# RGMII_PHY.net
KiCad netlist of a schematic drawn in Altium Designer
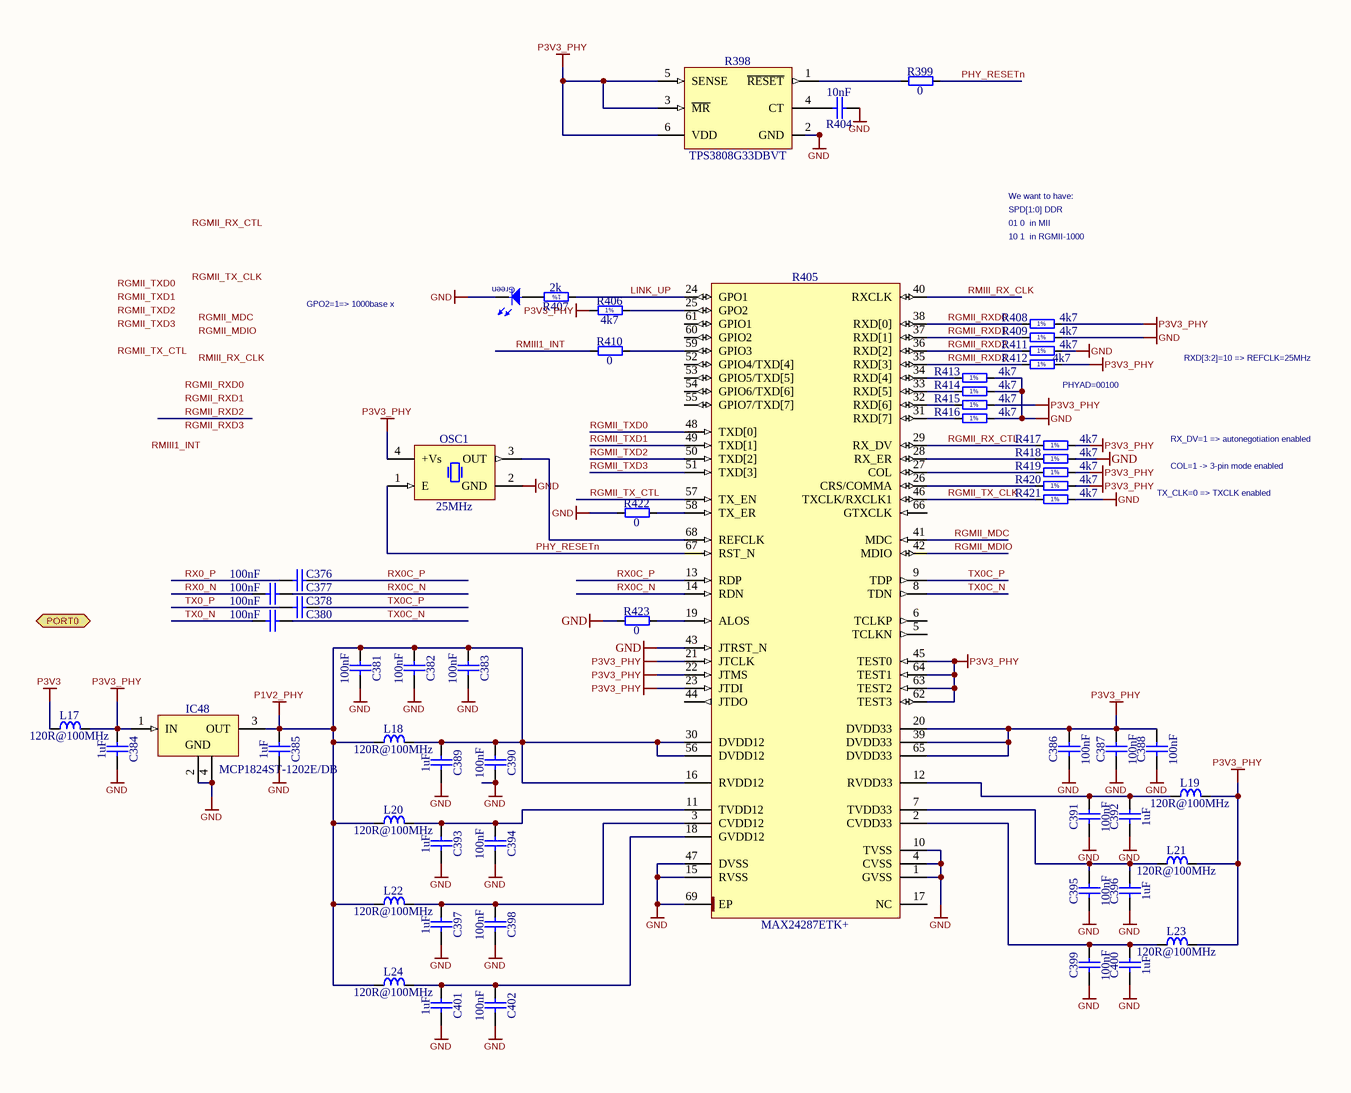
[diagram p0: RGMII_PHY.SchDoc]

(export (version "E")
  (design (tool "Eeschema 10.0.6"))
  (components
    (comp (ref "C376")
      (value "100nF")
      (footprint "CAPC0603X33N")
      (description "Non-polarised capacitor")
      (fields
        (field (name "MANUFACTURER PART NUMBER") "CC0201_100NF_6.3V_10%_X5R")
        (field (name "MANUFACTURER") "GENERIC")
        (field (name "AUTHOR") "CERN DEM JLC")
      )
      (libsource (lib "Capacitors") (part "Capacitor - non polarized"))
    )
    (comp (ref "C377")
      (value "100nF")
      (footprint "CAPC0603X33N")
      (description "Non-polarised capacitor")
      (fields
        (field (name "MANUFACTURER PART NUMBER") "CC0201_100NF_6.3V_10%_X5R")
        (field (name "MANUFACTURER") "GENERIC")
        (field (name "AUTHOR") "CERN DEM JLC")
      )
      (libsource (lib "Capacitors") (part "Capacitor - non polarized"))
    )
    (comp (ref "C378")
      (value "100nF")
      (footprint "CAPC0603X33N")
      (description "Non-polarised capacitor")
      (fields
        (field (name "MANUFACTURER PART NUMBER") "CC0201_100NF_6.3V_10%_X5R")
        (field (name "MANUFACTURER") "GENERIC")
        (field (name "AUTHOR") "CERN DEM JLC")
      )
      (libsource (lib "Capacitors") (part "Capacitor - non polarized"))
    )
    (comp (ref "C380")
      (value "100nF")
      (footprint "CAPC0603X33N")
      (description "Non-polarised capacitor")
      (fields
        (field (name "MANUFACTURER PART NUMBER") "CC0201_100NF_6.3V_10%_X5R")
        (field (name "MANUFACTURER") "GENERIC")
        (field (name "AUTHOR") "CERN DEM JLC")
      )
      (libsource (lib "Capacitors") (part "Capacitor - non polarized"))
    )
    (comp (ref "C381")
      (value "100nF")
      (footprint "CAPC0603X33N")
      (description "Non-polarised capacitor")
      (fields
        (field (name "MANUFACTURER PART NUMBER") "CC0201_100NF_6.3V_10%_X5R")
        (field (name "MANUFACTURER") "GENERIC")
        (field (name "AUTHOR") "CERN DEM JLC")
      )
      (libsource (lib "Capacitors") (part "Capacitor - non polarized"))
    )
    (comp (ref "C382")
      (value "100nF")
      (footprint "CAPC0603X33N")
      (description "Non-polarised capacitor")
      (fields
        (field (name "MANUFACTURER PART NUMBER") "CC0201_100NF_6.3V_10%_X5R")
        (field (name "MANUFACTURER") "GENERIC")
        (field (name "AUTHOR") "CERN DEM JLC")
      )
      (libsource (lib "Capacitors") (part "Capacitor - non polarized"))
    )
    (comp (ref "C383")
      (value "100nF")
      (footprint "CAPC0603X33N")
      (description "Non-polarised capacitor")
      (fields
        (field (name "MANUFACTURER PART NUMBER") "CC0201_100NF_6.3V_10%_X5R")
        (field (name "MANUFACTURER") "GENERIC")
        (field (name "AUTHOR") "CERN DEM JLC")
      )
      (libsource (lib "Capacitors") (part "Capacitor - non polarized"))
    )
    (comp (ref "C384")
      (value "1uF")
      (footprint "CAPC1005X55N")
      (description "Non-polarised capacitor")
      (fields
        (field (name "MANUFACTURER PART NUMBER") "CC0402_1UF_16V_10%_X5R")
        (field (name "MANUFACTURER") "GENERIC")
        (field (name "AUTHOR") "CERN DEM JLC")
      )
      (libsource (lib "Capacitors") (part "Capacitor - non polarized"))
    )
    (comp (ref "C385")
      (value "1uF")
      (footprint "CAPC1005X55N")
      (description "Non-polarised capacitor")
      (fields
        (field (name "MANUFACTURER PART NUMBER") "CC0402_1UF_16V_10%_X5R")
        (field (name "MANUFACTURER") "GENERIC")
        (field (name "AUTHOR") "CERN DEM JLC")
      )
      (libsource (lib "Capacitors") (part "Capacitor - non polarized"))
    )
    (comp (ref "C386")
      (value "100nF")
      (footprint "CAPC0603X33N")
      (description "Non-polarised capacitor")
      (fields
        (field (name "MANUFACTURER PART NUMBER") "CC0201_100NF_6.3V_10%_X5R")
        (field (name "MANUFACTURER") "GENERIC")
        (field (name "AUTHOR") "CERN DEM JLC")
      )
      (libsource (lib "Capacitors") (part "Capacitor - non polarized"))
    )
    (comp (ref "C387")
      (value "100nF")
      (footprint "CAPC0603X33N")
      (description "Non-polarised capacitor")
      (fields
        (field (name "MANUFACTURER PART NUMBER") "CC0201_100NF_6.3V_10%_X5R")
        (field (name "MANUFACTURER") "GENERIC")
        (field (name "AUTHOR") "CERN DEM JLC")
      )
      (libsource (lib "Capacitors") (part "Capacitor - non polarized"))
    )
    (comp (ref "C388")
      (value "100nF")
      (footprint "CAPC0603X33N")
      (description "Non-polarised capacitor")
      (fields
        (field (name "MANUFACTURER PART NUMBER") "CC0201_100NF_6.3V_10%_X5R")
        (field (name "MANUFACTURER") "GENERIC")
        (field (name "AUTHOR") "CERN DEM JLC")
      )
      (libsource (lib "Capacitors") (part "Capacitor - non polarized"))
    )
    (comp (ref "C389")
      (value "1uF")
      (footprint "CAPC1005X55N")
      (description "Non-polarised capacitor")
      (fields
        (field (name "MANUFACTURER PART NUMBER") "CC0402_1UF_16V_10%_X5R")
        (field (name "MANUFACTURER") "GENERIC")
        (field (name "AUTHOR") "CERN DEM JLC")
      )
      (libsource (lib "Capacitors") (part "Capacitor - non polarized"))
    )
    (comp (ref "C390")
      (value "100nF")
      (footprint "CAPC0603X33N")
      (description "Non-polarised capacitor")
      (fields
        (field (name "MANUFACTURER PART NUMBER") "CC0201_100NF_6.3V_10%_X5R")
        (field (name "MANUFACTURER") "GENERIC")
        (field (name "AUTHOR") "CERN DEM JLC")
      )
      (libsource (lib "Capacitors") (part "Capacitor - non polarized"))
    )
    (comp (ref "C391")
      (value "100nF")
      (footprint "CAPC0603X33N")
      (description "Non-polarised capacitor")
      (fields
        (field (name "MANUFACTURER PART NUMBER") "CC0201_100NF_6.3V_10%_X5R")
        (field (name "MANUFACTURER") "GENERIC")
        (field (name "AUTHOR") "CERN DEM JLC")
      )
      (libsource (lib "Capacitors") (part "Capacitor - non polarized"))
    )
    (comp (ref "C392")
      (value "1uF")
      (footprint "CAPC1005X55N")
      (description "Non-polarised capacitor")
      (fields
        (field (name "MANUFACTURER PART NUMBER") "CC0402_1UF_16V_10%_X5R")
        (field (name "MANUFACTURER") "GENERIC")
        (field (name "AUTHOR") "CERN DEM JLC")
      )
      (libsource (lib "Capacitors") (part "Capacitor - non polarized"))
    )
    (comp (ref "C393")
      (value "1uF")
      (footprint "CAPC1005X55N")
      (description "Non-polarised capacitor")
      (fields
        (field (name "MANUFACTURER PART NUMBER") "CC0402_1UF_16V_10%_X5R")
        (field (name "MANUFACTURER") "GENERIC")
        (field (name "AUTHOR") "CERN DEM JLC")
      )
      (libsource (lib "Capacitors") (part "Capacitor - non polarized"))
    )
    (comp (ref "C394")
      (value "100nF")
      (footprint "CAPC0603X33N")
      (description "Non-polarised capacitor")
      (fields
        (field (name "MANUFACTURER PART NUMBER") "CC0201_100NF_6.3V_10%_X5R")
        (field (name "MANUFACTURER") "GENERIC")
        (field (name "AUTHOR") "CERN DEM JLC")
      )
      (libsource (lib "Capacitors") (part "Capacitor - non polarized"))
    )
    (comp (ref "C395")
      (value "100nF")
      (footprint "CAPC0603X33N")
      (description "Non-polarised capacitor")
      (fields
        (field (name "MANUFACTURER PART NUMBER") "CC0201_100NF_6.3V_10%_X5R")
        (field (name "MANUFACTURER") "GENERIC")
        (field (name "AUTHOR") "CERN DEM JLC")
      )
      (libsource (lib "Capacitors") (part "Capacitor - non polarized"))
    )
    (comp (ref "C396")
      (value "1uF")
      (footprint "CAPC1005X55N")
      (description "Non-polarised capacitor")
      (fields
        (field (name "MANUFACTURER PART NUMBER") "CC0402_1UF_16V_10%_X5R")
        (field (name "MANUFACTURER") "GENERIC")
        (field (name "AUTHOR") "CERN DEM JLC")
      )
      (libsource (lib "Capacitors") (part "Capacitor - non polarized"))
    )
    (comp (ref "C397")
      (value "1uF")
      (footprint "CAPC1005X55N")
      (description "Non-polarised capacitor")
      (fields
        (field (name "MANUFACTURER PART NUMBER") "CC0402_1UF_16V_10%_X5R")
        (field (name "MANUFACTURER") "GENERIC")
        (field (name "AUTHOR") "CERN DEM JLC")
      )
      (libsource (lib "Capacitors") (part "Capacitor - non polarized"))
    )
    (comp (ref "C398")
      (value "100nF")
      (footprint "CAPC0603X33N")
      (description "Non-polarised capacitor")
      (fields
        (field (name "MANUFACTURER PART NUMBER") "CC0201_100NF_6.3V_10%_X5R")
        (field (name "MANUFACTURER") "GENERIC")
        (field (name "AUTHOR") "CERN DEM JLC")
      )
      (libsource (lib "Capacitors") (part "Capacitor - non polarized"))
    )
    (comp (ref "C399")
      (value "100nF")
      (footprint "CAPC0603X33N")
      (description "Non-polarised capacitor")
      (fields
        (field (name "MANUFACTURER PART NUMBER") "CC0201_100NF_6.3V_10%_X5R")
        (field (name "MANUFACTURER") "GENERIC")
        (field (name "AUTHOR") "CERN DEM JLC")
      )
      (libsource (lib "Capacitors") (part "Capacitor - non polarized"))
    )
    (comp (ref "C400")
      (value "1uF")
      (footprint "CAPC1005X55N")
      (description "Non-polarised capacitor")
      (fields
        (field (name "MANUFACTURER PART NUMBER") "CC0402_1UF_16V_10%_X5R")
        (field (name "MANUFACTURER") "GENERIC")
        (field (name "AUTHOR") "CERN DEM JLC")
      )
      (libsource (lib "Capacitors") (part "Capacitor - non polarized"))
    )
    (comp (ref "C401")
      (value "1uF")
      (footprint "CAPC1005X55N")
      (description "Non-polarised capacitor")
      (fields
        (field (name "MANUFACTURER PART NUMBER") "CC0402_1UF_16V_10%_X5R")
        (field (name "MANUFACTURER") "GENERIC")
        (field (name "AUTHOR") "CERN DEM JLC")
      )
      (libsource (lib "Capacitors") (part "Capacitor - non polarized"))
    )
    (comp (ref "C402")
      (value "100nF")
      (footprint "CAPC0603X33N")
      (description "Non-polarised capacitor")
      (fields
        (field (name "MANUFACTURER PART NUMBER") "CC0201_100NF_6.3V_10%_X5R")
        (field (name "MANUFACTURER") "GENERIC")
        (field (name "AUTHOR") "CERN DEM JLC")
      )
      (libsource (lib "Capacitors") (part "Capacitor - non polarized"))
    )
    (comp (ref "IC48")
      (value "MCP1824ST-1202E/DB")
      (footprint "SOT230P700X180-4N")
      (description "3-Terminal Regulator 1=IN 2=GND 3=OUT 4=GND")
      (fields (field (name "MANUFACTURER") "MICROCHIP TECHNOLOGY") (field (name "AUTHOR") "CERN DEM JLC"))
      (libsource (lib "ICs And Semiconductors") (part "REG3+1 1IN-2GND-3OUT+4GND"))
    )
    (comp (ref "L17")
      (value "120R@100MHz")
      (footprint "INDC1005X55N")
      (description "Inductor")
      (fields
        (field (name "MANUFACTURER PART NUMBER") "BLM15PX121SN1D")
        (field (name "MANUFACTURER") "MURATA")
        (field (name "AUTHOR") "CERN DEM JMW")
      )
      (libsource (lib "") (part "Inductor_1"))
    )
    (comp (ref "L18")
      (value "120R@100MHz")
      (footprint "INDC1005X55N")
      (description "Inductor")
      (fields
        (field (name "MANUFACTURER PART NUMBER") "BLM15PX121SN1D")
        (field (name "MANUFACTURER") "MURATA")
        (field (name "AUTHOR") "CERN DEM JMW")
      )
      (libsource (lib "Inductors & Transformers") (part "Inductor"))
    )
    (comp (ref "L19")
      (value "120R@100MHz")
      (footprint "INDC1005X55N")
      (description "Inductor")
      (fields
        (field (name "MANUFACTURER PART NUMBER") "BLM15PX121SN1D")
        (field (name "MANUFACTURER") "MURATA")
        (field (name "AUTHOR") "CERN DEM JMW")
      )
      (libsource (lib "") (part "Inductor_1"))
    )
    (comp (ref "L20")
      (value "120R@100MHz")
      (footprint "INDC1005X55N")
      (description "Inductor")
      (fields
        (field (name "MANUFACTURER PART NUMBER") "BLM15PX121SN1D")
        (field (name "MANUFACTURER") "MURATA")
        (field (name "AUTHOR") "CERN DEM JMW")
      )
      (libsource (lib "Inductors & Transformers") (part "Inductor"))
    )
    (comp (ref "L21")
      (value "120R@100MHz")
      (footprint "INDC1005X55N")
      (description "Inductor")
      (fields
        (field (name "MANUFACTURER PART NUMBER") "BLM15PX121SN1D")
        (field (name "MANUFACTURER") "MURATA")
        (field (name "AUTHOR") "CERN DEM JMW")
      )
      (libsource (lib "") (part "Inductor_1"))
    )
    (comp (ref "L22")
      (value "120R@100MHz")
      (footprint "INDC1005X55N")
      (description "Inductor")
      (fields
        (field (name "MANUFACTURER PART NUMBER") "BLM15PX121SN1D")
        (field (name "MANUFACTURER") "MURATA")
        (field (name "AUTHOR") "CERN DEM JMW")
      )
      (libsource (lib "Inductors & Transformers") (part "Inductor"))
    )
    (comp (ref "L23")
      (value "120R@100MHz")
      (footprint "INDC1005X55N")
      (description "Inductor")
      (fields
        (field (name "MANUFACTURER PART NUMBER") "BLM15PX121SN1D")
        (field (name "MANUFACTURER") "MURATA")
        (field (name "AUTHOR") "CERN DEM JMW")
      )
      (libsource (lib "") (part "Inductor_1"))
    )
    (comp (ref "L24")
      (value "120R@100MHz")
      (footprint "INDC1005X55N")
      (description "Inductor")
      (fields
        (field (name "MANUFACTURER PART NUMBER") "BLM15PX121SN1D")
        (field (name "MANUFACTURER") "MURATA")
        (field (name "AUTHOR") "CERN DEM JMW")
      )
      (libsource (lib "Inductors & Transformers") (part "Inductor"))
    )
    (comp (ref "LED1")
      (value "Green")
      (fields
        (field (name "MANUFACTURER PART NUMBER") "LG L29K-G2J1-24-Z")
        (field (name "MANUFACTURER") "OSRAM")
        (field (name "PART NUMBER") "LED_OSRAM_LG L29K-G2J1-24-Z")
        (field (name "AUTHOR") "CERN DEM JLC")
      )
      (libsource (lib "altium-import") (part "root_2__*"))
    )
    (comp (ref "OSC1")
      (value "25MHz")
      (footprint "OSC_IQD_CFPS-73")
      (description "Oscillator 4 pins 1=E 2=GND 3=OUT 4=+Vs")
      (fields
        (field (name "PART NUMBER") "OSC_25MHZ_IQD_LFSPXO018077")
        (field (name "MANUFACTURER") "IQD FREQUENCY PRODUCTS")
        (field (name "AUTHOR") "CERN DEM JLC")
      )
      (libsource (lib "ICs And Semiconductors") (part "Oscillator 1E 2GND 3OUT 4Vs"))
    )
    (comp (ref "R398")
      (value "TPS3808G33DBVT")
      (footprint "SOT95P280X145-6N")
      (description "Low Quiescent Current, Programmable-Delay Supervisory Circuit")
      (fields (field (name "MANUFACTURER") "TEXAS INSTRUMENTS") (field (name "AUTHOR") "CERN DEM JLC"))
      (libsource (lib "ICs And Semiconductors") (part "TPS3808xxxDBV"))
    )
    (comp (ref "R399")
      (value "0")
      (footprint "RESC1005X40N")
      (description "Resistor")
      (fields
        (field (name "MANUFACTURER PART NUMBER") "R0402_0R_JUMPER")
        (field (name "MANUFACTURER") "GENERIC")
        (field (name "AUTHOR") "CERN DEM JLC")
      )
      (libsource (lib "Resistors") (part "Resistor"))
    )
    (comp (ref "R404")
      (value "10nF")
      (footprint "CAPC1005X55N")
      (description "Non-polarised capacitor")
      (fields
        (field (name "MANUFACTURER PART NUMBER") "CC0402_10NF_16V_10%_X7R")
        (field (name "MANUFACTURER") "GENERIC")
        (field (name "AUTHOR") "CERN DEM JLC")
      )
      (libsource (lib "Capacitors") (part "Capacitor - non polarized"))
    )
    (comp (ref "R405")
      (value "MAX24287ETK+")
      (footprint "QFN40P800X800X80-69N-S635")
      (description "1Gbps Parallel-to-Serial MII Converter")
      (fields (field (name "MANUFACTURER") "MAXIM") (field (name "AUTHOR") "CERN DEM BC"))
      (libsource (lib "ICs And Semiconductors") (part "MAX24287"))
    )
    (comp (ref "R406")
      (value "4k7")
      (footprint "RESC1005X40N")
      (description "Resistor - 1%")
      (fields
        (field (name "MANUFACTURER PART NUMBER") "R0402_4K7_1%_0.0625W_100PPM")
        (field (name "MANUFACTURER") "GENERIC")
        (field (name "AUTHOR") "CERN DEM JLC")
      )
      (libsource (lib "Resistors") (part "Resistor - 1%"))
    )
    (comp (ref "R407")
      (value "2k")
      (footprint "RESC1005X40N")
      (description "Resistor - 1%")
      (fields
        (field (name "MANUFACTURER PART NUMBER") "R0402_2K_1%_0.0625W_100PPM")
        (field (name "MANUFACTURER") "GENERIC")
        (field (name "AUTHOR") "CERN DEM JLC")
      )
      (libsource (lib "Resistors") (part "Resistor - 1%"))
    )
    (comp (ref "R408")
      (value "4k7")
      (footprint "RESC1005X40N")
      (description "Resistor - 1%")
      (fields
        (field (name "MANUFACTURER PART NUMBER") "R0402_4K7_1%_0.0625W_100PPM")
        (field (name "MANUFACTURER") "GENERIC")
        (field (name "AUTHOR") "CERN DEM JLC")
      )
      (libsource (lib "Resistors") (part "Resistor - 1%"))
    )
    (comp (ref "R409")
      (value "4k7")
      (footprint "RESC1005X40N")
      (description "Resistor - 1%")
      (fields
        (field (name "MANUFACTURER PART NUMBER") "R0402_4K7_1%_0.0625W_100PPM")
        (field (name "MANUFACTURER") "GENERIC")
        (field (name "AUTHOR") "CERN DEM JLC")
      )
      (libsource (lib "Resistors") (part "Resistor - 1%"))
    )
    (comp (ref "R410")
      (value "0")
      (footprint "RESC1005X40N")
      (description "Resistor")
      (fields
        (field (name "MANUFACTURER PART NUMBER") "R0402_0R_JUMPER")
        (field (name "MANUFACTURER") "GENERIC")
        (field (name "AUTHOR") "CERN DEM JLC")
      )
      (libsource (lib "Resistors") (part "Resistor"))
    )
    (comp (ref "R411")
      (value "4k7")
      (footprint "RESC1005X40N")
      (description "Resistor - 1%")
      (fields
        (field (name "MANUFACTURER PART NUMBER") "R0402_4K7_1%_0.0625W_100PPM")
        (field (name "MANUFACTURER") "GENERIC")
        (field (name "AUTHOR") "CERN DEM JLC")
      )
      (libsource (lib "Resistors") (part "Resistor - 1%"))
    )
    (comp (ref "R412")
      (value "4k7")
      (footprint "RESC1005X40N")
      (description "Resistor - 1%")
      (fields
        (field (name "MANUFACTURER PART NUMBER") "R0402_4K7_1%_0.0625W_100PPM")
        (field (name "MANUFACTURER") "GENERIC")
        (field (name "AUTHOR") "CERN DEM JLC")
      )
      (libsource (lib "Resistors") (part "Resistor - 1%"))
    )
    (comp (ref "R413")
      (value "4k7")
      (footprint "RESC1005X40N")
      (description "Resistor - 1%")
      (fields
        (field (name "MANUFACTURER PART NUMBER") "R0402_4K7_1%_0.0625W_100PPM")
        (field (name "MANUFACTURER") "GENERIC")
        (field (name "AUTHOR") "CERN DEM JLC")
      )
      (libsource (lib "Resistors") (part "Resistor - 1%"))
    )
    (comp (ref "R414")
      (value "4k7")
      (footprint "RESC1005X40N")
      (description "Resistor - 1%")
      (fields
        (field (name "MANUFACTURER PART NUMBER") "R0402_4K7_1%_0.0625W_100PPM")
        (field (name "MANUFACTURER") "GENERIC")
        (field (name "AUTHOR") "CERN DEM JLC")
      )
      (libsource (lib "Resistors") (part "Resistor - 1%"))
    )
    (comp (ref "R415")
      (value "4k7")
      (footprint "RESC1005X40N")
      (description "Resistor - 1%")
      (fields
        (field (name "MANUFACTURER PART NUMBER") "R0402_4K7_1%_0.0625W_100PPM")
        (field (name "MANUFACTURER") "GENERIC")
        (field (name "AUTHOR") "CERN DEM JLC")
      )
      (libsource (lib "Resistors") (part "Resistor - 1%"))
    )
    (comp (ref "R416")
      (value "4k7")
      (footprint "RESC1005X40N")
      (description "Resistor - 1%")
      (fields
        (field (name "MANUFACTURER PART NUMBER") "R0402_4K7_1%_0.0625W_100PPM")
        (field (name "MANUFACTURER") "GENERIC")
        (field (name "AUTHOR") "CERN DEM JLC")
      )
      (libsource (lib "Resistors") (part "Resistor - 1%"))
    )
    (comp (ref "R417")
      (value "4k7")
      (footprint "RESC1005X40N")
      (description "Resistor - 1%")
      (fields
        (field (name "MANUFACTURER PART NUMBER") "R0402_4K7_1%_0.0625W_100PPM")
        (field (name "MANUFACTURER") "GENERIC")
        (field (name "AUTHOR") "CERN DEM JLC")
      )
      (libsource (lib "Resistors") (part "Resistor - 1%"))
    )
    (comp (ref "R418")
      (value "4k7")
      (footprint "RESC1005X40N")
      (description "Resistor - 1%")
      (fields
        (field (name "MANUFACTURER PART NUMBER") "R0402_4K7_1%_0.0625W_100PPM")
        (field (name "MANUFACTURER") "GENERIC")
        (field (name "AUTHOR") "CERN DEM JLC")
      )
      (libsource (lib "Resistors") (part "Resistor - 1%"))
    )
    (comp (ref "R419")
      (value "4k7")
      (footprint "RESC1005X40N")
      (description "Resistor - 1%")
      (fields
        (field (name "MANUFACTURER PART NUMBER") "R0402_4K7_1%_0.0625W_100PPM")
        (field (name "MANUFACTURER") "GENERIC")
        (field (name "AUTHOR") "CERN DEM JLC")
      )
      (libsource (lib "Resistors") (part "Resistor - 1%"))
    )
    (comp (ref "R420")
      (value "4k7")
      (footprint "RESC1005X40N")
      (description "Resistor - 1%")
      (fields
        (field (name "MANUFACTURER PART NUMBER") "R0402_4K7_1%_0.0625W_100PPM")
        (field (name "MANUFACTURER") "GENERIC")
        (field (name "AUTHOR") "CERN DEM JLC")
      )
      (libsource (lib "Resistors") (part "Resistor - 1%"))
    )
    (comp (ref "R421")
      (value "4k7")
      (footprint "RESC1005X40N")
      (description "Resistor - 1%")
      (fields
        (field (name "MANUFACTURER PART NUMBER") "R0402_4K7_1%_0.0625W_100PPM")
        (field (name "MANUFACTURER") "GENERIC")
        (field (name "AUTHOR") "CERN DEM JLC")
      )
      (libsource (lib "Resistors") (part "Resistor - 1%"))
    )
    (comp (ref "R422")
      (value "0")
      (footprint "RESC1005X40N")
      (description "Resistor")
      (fields
        (field (name "MANUFACTURER PART NUMBER") "R0402_0R_JUMPER")
        (field (name "MANUFACTURER") "GENERIC")
        (field (name "AUTHOR") "CERN DEM JLC")
      )
      (libsource (lib "Resistors") (part "Resistor"))
    )
    (comp (ref "R423")
      (value "0")
      (footprint "RESC1005X40N")
      (description "Resistor")
      (fields
        (field (name "MANUFACTURER PART NUMBER") "R0402_0R_JUMPER")
        (field (name "MANUFACTURER") "GENERIC")
        (field (name "AUTHOR") "CERN DEM JLC")
      )
      (libsource (lib "Resistors") (part "Resistor"))
    )
  )
  (nets
    (net (code "1") (name "/LINK_UP") (class "Default")
      (node (ref "R405") (pin "24") (pinfunction "GPO1_24") (pintype "bidirectional"))
      (node (ref "R407") (pin "1") (pinfunction "1_1") (pintype "passive"))
    )
    (net (code "2") (name "/PHY_RESETn") (class "Default")
      (node (ref "OSC1") (pin "1") (pinfunction "E_1") (pintype "input"))
      (node (ref "R399") (pin "2") (pinfunction "2_2") (pintype "passive"))
      (node (ref "R405") (pin "67") (pinfunction "RST_N_67") (pintype "input"))
    )
    (net (code "4") (name "/RGMII_MDC") (class "Default")
      (node (ref "R405") (pin "41") (pinfunction "MDC_41") (pintype "input"))
    )
    (net (code "5") (name "/RGMII_MDIO") (class "Default")
      (node (ref "R405") (pin "42") (pinfunction "MDIO_42") (pintype "bidirectional"))
    )
    (net (code "6") (name "/RGMII_RXD0") (class "Default")
      (node (ref "R405") (pin "38") (pinfunction "RXD[0]_38") (pintype "bidirectional"))
      (node (ref "R408") (pin "1") (pinfunction "1_1") (pintype "passive"))
    )
    (net (code "7") (name "/RGMII_RXD1") (class "Default")
      (node (ref "R405") (pin "37") (pinfunction "RXD[1]_37") (pintype "bidirectional"))
      (node (ref "R409") (pin "1") (pinfunction "1_1") (pintype "passive"))
    )
    (net (code "8") (name "/RGMII_RXD2") (class "Default")
      (node (ref "R405") (pin "36") (pinfunction "RXD[2]_36") (pintype "bidirectional"))
      (node (ref "R411") (pin "1") (pinfunction "1_1") (pintype "passive"))
    )
    (net (code "9") (name "/RGMII_RXD3") (class "Default")
      (node (ref "R405") (pin "35") (pinfunction "RXD[3]_35") (pintype "bidirectional"))
      (node (ref "R412") (pin "1") (pinfunction "1_1") (pintype "passive"))
    )
    (net (code "10") (name "/RGMII_RX_CTL") (class "Default")
      (node (ref "R405") (pin "29") (pinfunction "RX_DV_29") (pintype "bidirectional"))
      (node (ref "R417") (pin "1") (pinfunction "1_1") (pintype "passive"))
    )
    (net (code "11") (name "/RGMII_TXD0") (class "Default")
      (node (ref "R405") (pin "48") (pinfunction "TXD[0]_48") (pintype "input"))
    )
    (net (code "12") (name "/RGMII_TXD1") (class "Default")
      (node (ref "R405") (pin "49") (pinfunction "TXD[1]_49") (pintype "input"))
    )
    (net (code "13") (name "/RGMII_TXD2") (class "Default")
      (node (ref "R405") (pin "50") (pinfunction "TXD[2]_50") (pintype "input"))
    )
    (net (code "14") (name "/RGMII_TXD3") (class "Default")
      (node (ref "R405") (pin "51") (pinfunction "TXD[3]_51") (pintype "input"))
    )
    (net (code "15") (name "/RGMII_TX_CLK") (class "Default")
      (node (ref "R405") (pin "46") (pinfunction "TXCLK/RXCLK1_46") (pintype "bidirectional"))
      (node (ref "R421") (pin "1") (pinfunction "1_1") (pintype "passive"))
    )
    (net (code "16") (name "/RGMII_TX_CTL") (class "Default")
      (node (ref "R405") (pin "57") (pinfunction "TX_EN_57") (pintype "input"))
    )
    (net (code "17") (name "/RMIII1_INT") (class "Default")
      (node (ref "R410") (pin "1") (pinfunction "1_1") (pintype "passive"))
    )
    (net (code "18") (name "/RMIII_RX_CLK") (class "Default")
      (node (ref "R405") (pin "40") (pinfunction "RXCLK_40") (pintype "bidirectional"))
    )
    (net (code "19") (name "/RX0C_N") (class "Default")
      (node (ref "C377") (pin "2") (pinfunction "2_2") (pintype "passive"))
      (node (ref "R405") (pin "14") (pinfunction "RDN_14") (pintype "input"))
    )
    (net (code "20") (name "/RX0C_P") (class "Default")
      (node (ref "C376") (pin "2") (pinfunction "2_2") (pintype "passive"))
      (node (ref "R405") (pin "13") (pinfunction "RDP_13") (pintype "input"))
    )
    (net (code "21") (name "/RX0_N") (class "Default")
      (node (ref "C377") (pin "1") (pinfunction "1_1") (pintype "passive"))
    )
    (net (code "22") (name "/RX0_P") (class "Default")
      (node (ref "C376") (pin "1") (pinfunction "1_1") (pintype "passive"))
    )
    (net (code "23") (name "/TX0C_N") (class "Default")
      (node (ref "C380") (pin "2") (pinfunction "2_2") (pintype "passive"))
      (node (ref "R405") (pin "8") (pinfunction "TDN_8") (pintype "output"))
    )
    (net (code "24") (name "/TX0C_P") (class "Default")
      (node (ref "C378") (pin "2") (pinfunction "2_2") (pintype "passive"))
      (node (ref "R405") (pin "9") (pinfunction "TDP_9") (pintype "output"))
    )
    (net (code "25") (name "/TX0_N") (class "Default")
      (node (ref "C380") (pin "1") (pinfunction "1_1") (pintype "passive"))
    )
    (net (code "26") (name "/TX0_P") (class "Default")
      (node (ref "C378") (pin "1") (pinfunction "1_1") (pintype "passive"))
    )
    (net (code "27") (name "GND") (class "Default")
      (node (ref "C381") (pin "1") (pinfunction "1_1") (pintype "passive"))
      (node (ref "C382") (pin "1") (pinfunction "1_1") (pintype "passive"))
      (node (ref "C383") (pin "1") (pinfunction "1_1") (pintype "passive"))
      (node (ref "C384") (pin "1") (pinfunction "1_1") (pintype "passive"))
      (node (ref "C385") (pin "1") (pinfunction "1_1") (pintype "passive"))
      (node (ref "C386") (pin "1") (pinfunction "1_1") (pintype "passive"))
      (node (ref "C387") (pin "1") (pinfunction "1_1") (pintype "passive"))
      (node (ref "C388") (pin "1") (pinfunction "1_1") (pintype "passive"))
      (node (ref "C389") (pin "1") (pinfunction "1_1") (pintype "passive"))
      (node (ref "C390") (pin "1") (pinfunction "1_1") (pintype "passive"))
      (node (ref "C391") (pin "1") (pinfunction "1_1") (pintype "passive"))
      (node (ref "C392") (pin "1") (pinfunction "1_1") (pintype "passive"))
      (node (ref "C393") (pin "1") (pinfunction "1_1") (pintype "passive"))
      (node (ref "C394") (pin "1") (pinfunction "1_1") (pintype "passive"))
      (node (ref "C395") (pin "1") (pinfunction "1_1") (pintype "passive"))
      (node (ref "C396") (pin "1") (pinfunction "1_1") (pintype "passive"))
      (node (ref "C397") (pin "1") (pinfunction "1_1") (pintype "passive"))
      (node (ref "C398") (pin "1") (pinfunction "1_1") (pintype "passive"))
      (node (ref "C399") (pin "1") (pinfunction "1_1") (pintype "passive"))
      (node (ref "C400") (pin "1") (pinfunction "1_1") (pintype "passive"))
      (node (ref "C401") (pin "1") (pinfunction "1_1") (pintype "passive"))
      (node (ref "C402") (pin "1") (pinfunction "1_1") (pintype "passive"))
      (node (ref "IC48") (pin "2") (pinfunction "GND_2") (pintype "power_in"))
      (node (ref "IC48") (pin "4") (pinfunction "GND_4") (pintype "power_in"))
      (node (ref "LED1") (pin "1") (pinfunction "C_1") (pintype "passive"))
      (node (ref "OSC1") (pin "2") (pinfunction "GND_2") (pintype "power_in"))
      (node (ref "R398") (pin "2") (pinfunction "GND_2") (pintype "power_in"))
      (node (ref "R404") (pin "1") (pinfunction "1_1") (pintype "passive"))
      (node (ref "R405") (pin "1") (pinfunction "GVSS_1") (pintype "power_in"))
      (node (ref "R405") (pin "10") (pinfunction "TVSS_10") (pintype "power_in"))
      (node (ref "R405") (pin "15") (pinfunction "RVSS_15") (pintype "power_in"))
      (node (ref "R405") (pin "4") (pinfunction "CVSS_4") (pintype "power_in"))
      (node (ref "R405") (pin "43") (pinfunction "JTRST_N_43") (pintype "input"))
      (node (ref "R405") (pin "47") (pinfunction "DVSS_47") (pintype "power_in"))
      (node (ref "R405") (pin "69") (pinfunction "EP_69") (pintype "power_in"))
      (node (ref "R409") (pin "2") (pinfunction "2_2") (pintype "passive"))
      (node (ref "R411") (pin "2") (pinfunction "2_2") (pintype "passive"))
      (node (ref "R413") (pin "2") (pinfunction "2_2") (pintype "passive"))
      (node (ref "R414") (pin "2") (pinfunction "2_2") (pintype "passive"))
      (node (ref "R416") (pin "2") (pinfunction "2_2") (pintype "passive"))
      (node (ref "R418") (pin "2") (pinfunction "2_2") (pintype "passive"))
      (node (ref "R421") (pin "2") (pinfunction "2_2") (pintype "passive"))
      (node (ref "R422") (pin "1") (pinfunction "1_1") (pintype "passive"))
      (node (ref "R423") (pin "1") (pinfunction "1_1") (pintype "passive"))
    )
    (net (code "28") (name "Net-(LED1-A)") (class "Default")
      (node (ref "LED1") (pin "2") (pinfunction "A_2") (pintype "passive"))
      (node (ref "R407") (pin "2") (pinfunction "2_2") (pintype "passive"))
    )
    (net (code "29") (name "Net-(OSC1-OUT)") (class "Default")
      (node (ref "OSC1") (pin "3") (pinfunction "OUT_3") (pintype "output"))
      (node (ref "R405") (pin "68") (pinfunction "REFCLK_68") (pintype "input"))
    )
    (net (code "30") (name "Net-(R398-CT)") (class "Default")
      (node (ref "R398") (pin "4") (pinfunction "CT_4") (pintype "passive"))
      (node (ref "R404") (pin "2") (pinfunction "2_2") (pintype "passive"))
    )
    (net (code "31") (name "Net-(R398-~{RESET})") (class "Default")
      (node (ref "R398") (pin "1") (pinfunction "~{RESET}_1") (pintype "output"))
      (node (ref "R399") (pin "1") (pinfunction "1_1") (pintype "passive"))
    )
    (net (code "32") (name "Net-(R405-ALOS)") (class "Default")
      (node (ref "R405") (pin "19") (pinfunction "ALOS_19") (pintype "input"))
      (node (ref "R423") (pin "2") (pinfunction "2_2") (pintype "passive"))
    )
    (net (code "33") (name "Net-(R405-COL)") (class "Default")
      (node (ref "R405") (pin "27") (pinfunction "COL_27") (pintype "bidirectional"))
      (node (ref "R419") (pin "1") (pinfunction "1_1") (pintype "passive"))
    )
    (net (code "34") (name "Net-(R405-CRS{slash}COMMA)") (class "Default")
      (node (ref "R405") (pin "26") (pinfunction "CRS/COMMA_26") (pintype "bidirectional"))
      (node (ref "R420") (pin "1") (pinfunction "1_1") (pintype "passive"))
    )
    (net (code "35") (name "Net-(R405-CVDD12)") (class "Default")
      (node (ref "C397") (pin "2") (pinfunction "2_2") (pintype "passive"))
      (node (ref "C398") (pin "2") (pinfunction "2_2") (pintype "passive"))
      (node (ref "L22") (pin "1") (pinfunction "1_1") (pintype "passive"))
      (node (ref "R405") (pin "3") (pinfunction "CVDD12_3") (pintype "power_in"))
    )
    (net (code "36") (name "Net-(R405-CVDD33)") (class "Default")
      (node (ref "C399") (pin "2") (pinfunction "2_2") (pintype "passive"))
      (node (ref "C400") (pin "2") (pinfunction "2_2") (pintype "passive"))
      (node (ref "L23") (pin "1") (pinfunction "1_1") (pintype "passive"))
      (node (ref "R405") (pin "2") (pinfunction "CVDD33_2") (pintype "power_in"))
    )
    (net (code "37") (name "Net-(R405-GPIO3)") (class "Default")
      (node (ref "R405") (pin "59") (pinfunction "GPIO3_59") (pintype "bidirectional"))
      (node (ref "R410") (pin "2") (pinfunction "2_2") (pintype "passive"))
    )
    (net (code "38") (name "Net-(R405-GPO2)") (class "Default")
      (node (ref "R405") (pin "25") (pinfunction "GPO2_25") (pintype "bidirectional"))
      (node (ref "R406") (pin "2") (pinfunction "2_2") (pintype "passive"))
    )
    (net (code "39") (name "Net-(R405-GVDD12)") (class "Default")
      (node (ref "C401") (pin "2") (pinfunction "2_2") (pintype "passive"))
      (node (ref "C402") (pin "2") (pinfunction "2_2") (pintype "passive"))
      (node (ref "L24") (pin "1") (pinfunction "1_1") (pintype "passive"))
      (node (ref "R405") (pin "18") (pinfunction "GVDD12_18") (pintype "power_in"))
    )
    (net (code "40") (name "Net-(R405-RVDD33)") (class "Default")
      (node (ref "C391") (pin "2") (pinfunction "2_2") (pintype "passive"))
      (node (ref "C392") (pin "2") (pinfunction "2_2") (pintype "passive"))
      (node (ref "L19") (pin "1") (pinfunction "1_1") (pintype "passive"))
      (node (ref "R405") (pin "12") (pinfunction "RVDD33_12") (pintype "power_in"))
    )
    (net (code "41") (name "Net-(R405-RXD[4])") (class "Default")
      (node (ref "R405") (pin "34") (pinfunction "RXD[4]_34") (pintype "bidirectional"))
      (node (ref "R413") (pin "1") (pinfunction "1_1") (pintype "passive"))
    )
    (net (code "42") (name "Net-(R405-RXD[5])") (class "Default")
      (node (ref "R405") (pin "33") (pinfunction "RXD[5]_33") (pintype "bidirectional"))
      (node (ref "R414") (pin "1") (pinfunction "1_1") (pintype "passive"))
    )
    (net (code "43") (name "Net-(R405-RXD[6])") (class "Default")
      (node (ref "R405") (pin "32") (pinfunction "RXD[6]_32") (pintype "bidirectional"))
      (node (ref "R415") (pin "1") (pinfunction "1_1") (pintype "passive"))
    )
    (net (code "44") (name "Net-(R405-RXD[7])") (class "Default")
      (node (ref "R405") (pin "31") (pinfunction "RXD[7]_31") (pintype "bidirectional"))
      (node (ref "R416") (pin "1") (pinfunction "1_1") (pintype "passive"))
    )
    (net (code "45") (name "Net-(R405-RX_ER)") (class "Default")
      (node (ref "R405") (pin "28") (pinfunction "RX_ER_28") (pintype "bidirectional"))
      (node (ref "R418") (pin "1") (pinfunction "1_1") (pintype "passive"))
    )
    (net (code "46") (name "Net-(R405-TVDD12)") (class "Default")
      (node (ref "C393") (pin "2") (pinfunction "2_2") (pintype "passive"))
      (node (ref "C394") (pin "2") (pinfunction "2_2") (pintype "passive"))
      (node (ref "L20") (pin "1") (pinfunction "1_1") (pintype "passive"))
      (node (ref "R405") (pin "11") (pinfunction "TVDD12_11") (pintype "power_in"))
    )
    (net (code "47") (name "Net-(R405-TVDD33)") (class "Default")
      (node (ref "C395") (pin "2") (pinfunction "2_2") (pintype "passive"))
      (node (ref "C396") (pin "2") (pinfunction "2_2") (pintype "passive"))
      (node (ref "L21") (pin "1") (pinfunction "1_1") (pintype "passive"))
      (node (ref "R405") (pin "7") (pinfunction "TVDD33_7") (pintype "power_in"))
    )
    (net (code "48") (name "Net-(R405-TX_ER)") (class "Default")
      (node (ref "R405") (pin "58") (pinfunction "TX_ER_58") (pintype "input"))
      (node (ref "R422") (pin "2") (pinfunction "2_2") (pintype "passive"))
    )
    (net (code "49") (name "P1V2_PHY") (class "Default")
      (node (ref "C381") (pin "2") (pinfunction "2_2") (pintype "passive"))
      (node (ref "C382") (pin "2") (pinfunction "2_2") (pintype "passive"))
      (node (ref "C383") (pin "2") (pinfunction "2_2") (pintype "passive"))
      (node (ref "C385") (pin "2") (pinfunction "2_2") (pintype "passive"))
      (node (ref "C389") (pin "2") (pinfunction "2_2") (pintype "passive"))
      (node (ref "C390") (pin "2") (pinfunction "2_2") (pintype "passive"))
      (node (ref "IC48") (pin "3") (pinfunction "OUT_3") (pintype "power_in"))
      (node (ref "L18") (pin "1") (pinfunction "1_1") (pintype "passive"))
      (node (ref "L18") (pin "2") (pinfunction "2_2") (pintype "passive"))
      (node (ref "L20") (pin "2") (pinfunction "2_2") (pintype "passive"))
      (node (ref "L22") (pin "2") (pinfunction "2_2") (pintype "passive"))
      (node (ref "L24") (pin "2") (pinfunction "2_2") (pintype "passive"))
      (node (ref "R405") (pin "16") (pinfunction "RVDD12_16") (pintype "power_in"))
      (node (ref "R405") (pin "30") (pinfunction "DVDD12_30") (pintype "power_in"))
      (node (ref "R405") (pin "56") (pinfunction "DVDD12_56") (pintype "power_in"))
    )
    (net (code "50") (name "P3V3") (class "Default")
      (node (ref "L17") (pin "1") (pinfunction "1_1") (pintype "passive"))
    )
    (net (code "51") (name "P3V3_PHY") (class "Default")
      (node (ref "C384") (pin "2") (pinfunction "2_2") (pintype "passive"))
      (node (ref "C386") (pin "2") (pinfunction "2_2") (pintype "passive"))
      (node (ref "C387") (pin "2") (pinfunction "2_2") (pintype "passive"))
      (node (ref "C388") (pin "2") (pinfunction "2_2") (pintype "passive"))
      (node (ref "IC48") (pin "1") (pinfunction "IN_1") (pintype "input"))
      (node (ref "L17") (pin "2") (pinfunction "2_2") (pintype "passive"))
      (node (ref "L19") (pin "2") (pinfunction "2_2") (pintype "passive"))
      (node (ref "L21") (pin "2") (pinfunction "2_2") (pintype "passive"))
      (node (ref "L23") (pin "2") (pinfunction "2_2") (pintype "passive"))
      (node (ref "OSC1") (pin "4") (pinfunction "+Vs_4") (pintype "power_in"))
      (node (ref "R398") (pin "3") (pinfunction "~{MR}_3") (pintype "input"))
      (node (ref "R398") (pin "5") (pinfunction "SENSE_5") (pintype "input"))
      (node (ref "R398") (pin "6") (pinfunction "VDD_6") (pintype "power_in"))
      (node (ref "R405") (pin "20") (pinfunction "DVDD33_20") (pintype "power_in"))
      (node (ref "R405") (pin "21") (pinfunction "JTCLK_21") (pintype "input"))
      (node (ref "R405") (pin "22") (pinfunction "JTMS_22") (pintype "input"))
      (node (ref "R405") (pin "23") (pinfunction "JTDI_23") (pintype "input"))
      (node (ref "R405") (pin "39") (pinfunction "DVDD33_39") (pintype "power_in"))
      (node (ref "R405") (pin "45") (pinfunction "TEST0_45") (pintype "input"))
      (node (ref "R405") (pin "62") (pinfunction "TEST3_62") (pintype "bidirectional"))
      (node (ref "R405") (pin "63") (pinfunction "TEST2_63") (pintype "input"))
      (node (ref "R405") (pin "64") (pinfunction "TEST1_64") (pintype "input"))
      (node (ref "R405") (pin "65") (pinfunction "DVDD33_65") (pintype "power_in"))
      (node (ref "R406") (pin "1") (pinfunction "1_1") (pintype "passive"))
      (node (ref "R408") (pin "2") (pinfunction "2_2") (pintype "passive"))
      (node (ref "R412") (pin "2") (pinfunction "2_2") (pintype "passive"))
      (node (ref "R415") (pin "2") (pinfunction "2_2") (pintype "passive"))
      (node (ref "R417") (pin "2") (pinfunction "2_2") (pintype "passive"))
      (node (ref "R419") (pin "2") (pinfunction "2_2") (pintype "passive"))
      (node (ref "R420") (pin "2") (pinfunction "2_2") (pintype "passive"))
    )
    (net (code "52") (name "unconnected-(R405-GPIO1-Pad61)") (class "Default")
      (node (ref "R405") (pin "61") (pinfunction "GPIO1_61") (pintype "bidirectional"))
    )
    (net (code "53") (name "unconnected-(R405-GPIO2-Pad60)") (class "Default")
      (node (ref "R405") (pin "60") (pinfunction "GPIO2_60") (pintype "bidirectional"))
    )
    (net (code "54") (name "unconnected-(R405-GPIO4{slash}TXD[4]-Pad52)") (class "Default")
      (node (ref "R405") (pin "52") (pinfunction "GPIO4/TXD[4]_52") (pintype "bidirectional"))
    )
    (net (code "55") (name "unconnected-(R405-GPIO5{slash}TXD[5]-Pad53)") (class "Default")
      (node (ref "R405") (pin "53") (pinfunction "GPIO5/TXD[5]_53") (pintype "bidirectional"))
    )
    (net (code "56") (name "unconnected-(R405-GPIO6{slash}TXD[6]-Pad54)") (class "Default")
      (node (ref "R405") (pin "54") (pinfunction "GPIO6/TXD[6]_54") (pintype "bidirectional"))
    )
    (net (code "57") (name "unconnected-(R405-GPIO7{slash}TXD[7]-Pad55)") (class "Default")
      (node (ref "R405") (pin "55") (pinfunction "GPIO7/TXD[7]_55") (pintype "bidirectional"))
    )
    (net (code "58") (name "unconnected-(R405-GTXCLK-Pad66)") (class "Default")
      (node (ref "R405") (pin "66") (pinfunction "GTXCLK_66") (pintype "input"))
    )
    (net (code "59") (name "unconnected-(R405-JTDO-Pad44)") (class "Default")
      (node (ref "R405") (pin "44") (pinfunction "JTDO_44") (pintype "output"))
    )
    (net (code "60") (name "unconnected-(R405-NC-Pad17)") (class "Default")
      (node (ref "R405") (pin "17") (pinfunction "NC_17") (pintype "passive"))
    )
    (net (code "61") (name "unconnected-(R405-TCLKN-Pad5)") (class "Default")
      (node (ref "R405") (pin "5") (pinfunction "TCLKN_5") (pintype "output"))
    )
    (net (code "62") (name "unconnected-(R405-TCLKP-Pad6)") (class "Default")
      (node (ref "R405") (pin "6") (pinfunction "TCLKP_6") (pintype "output"))
    )
  )
)
